# Power-Supply.net
KiCad netlist of a schematic drawn in Altium Designer
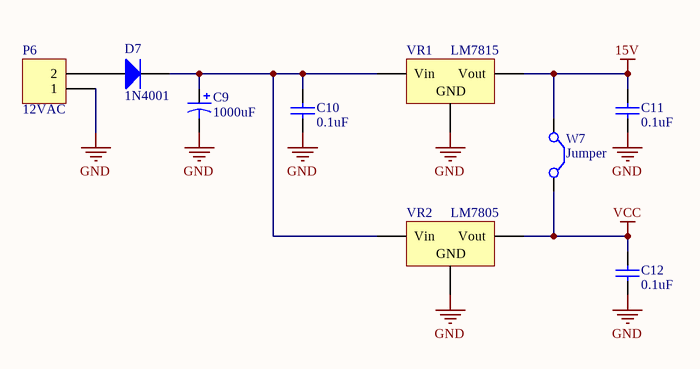
[diagram p0: Power-Supply.SchDoc]

(export (version "E")
  (design (tool "Eeschema 10.0.6"))
  (components
    (comp (ref "C9")
      (value "1000uF")
      (footprint "toko-Embedded:E3,5-10")
      (description "Polarized Capacitor (Radial)")
      (fields (field (name "PUBLISHER") "Altium Limited"))
      (libsource (lib "Miscellaneous Devices") (part "Cap Pol1"))
    )
    (comp (ref "C10")
      (value "0.1uF")
      (footprint "toko-Embedded:C025-024X044")
      (description "Capacitor")
      (fields (field (name "PUBLISHER") "Altium Limited"))
      (libsource (lib "Miscellaneous Devices") (part "Cap"))
    )
    (comp (ref "C11")
      (value "0.1uF")
      (footprint "toko-Embedded:C025-024X044")
      (description "Capacitor")
      (fields (field (name "PUBLISHER") "Altium Limited"))
      (libsource (lib "Miscellaneous Devices") (part "Cap"))
    )
    (comp (ref "C12")
      (value "0.1uF")
      (footprint "toko-Embedded:C025-024X044")
      (description "Capacitor")
      (fields (field (name "PUBLISHER") "Altium Limited"))
      (libsource (lib "Miscellaneous Devices") (part "Cap"))
    )
    (comp (ref "D7")
      (value "1N4001")
      (footprint "toko-Embedded:DO41-10")
      (description "Default Diode")
      (fields (field (name "PUBLISHER") "Altium Limited"))
      (libsource (lib "Miscellaneous Devices") (part "Diode"))
    )
    (comp (ref "P6")
      (value "12VAC")
      (footprint "toko-Embedded:6410-02")
      (description "Header, 2-Pin")
      (fields (field (name "PUBLISHER") "Altium Limited"))
      (libsource (lib "Miscellaneous Connectors") (part "Header 2"))
    )
    (comp (ref "VR1")
      (value "LM7815")
      (footprint "toko-Embedded:TO220V")
      (description "Voltage Regulator")
      (fields (field (name "PUBLISHER") "Altium Limited"))
      (libsource (lib "Miscellaneous Devices") (part "Volt Reg"))
    )
    (comp (ref "VR2")
      (value "LM7805")
      (footprint "toko-Embedded:TO220V")
      (description "Voltage Regulator")
      (fields (field (name "PUBLISHER") "Altium Limited"))
      (libsource (lib "Miscellaneous Devices") (part "Volt Reg"))
    )
    (comp (ref "W7")
      (value "Jumper")
      (footprint "Miscellaneous Connectors:HDR1X2")
      (description "Jumper Wire")
      (fields (field (name "PUBLISHER") "Altium Limited"))
      (libsource (lib "Miscellaneous Devices") (part "Jumper"))
    )
  )
  (nets
    (net (code "1") (name "15V") (class "Default")
      (node (ref "C11") (pin "2") (pinfunction "2_2") (pintype "passive"))
      (node (ref "VR1") (pin "3") (pinfunction "Vout_3") (pintype "passive"))
      (node (ref "W7") (pin "1") (pinfunction "C1_1") (pintype "passive"))
    )
    (net (code "2") (name "GND") (class "Default")
      (node (ref "C10") (pin "1") (pinfunction "1_1") (pintype "passive"))
      (node (ref "C11") (pin "1") (pinfunction "1_1") (pintype "passive"))
      (node (ref "C12") (pin "1") (pinfunction "1_1") (pintype "passive"))
      (node (ref "C9") (pin "2") (pinfunction "2_2") (pintype "passive"))
      (node (ref "P6") (pin "1") (pinfunction "1_1") (pintype "passive"))
      (node (ref "VR1") (pin "2") (pinfunction "GND_2") (pintype "passive"))
      (node (ref "VR2") (pin "2") (pinfunction "GND_2") (pintype "passive"))
    )
    (net (code "3") (name "Net-(D7-A)") (class "Default")
      (node (ref "D7") (pin "1") (pinfunction "A_1") (pintype "passive"))
      (node (ref "P6") (pin "2") (pinfunction "2_2") (pintype "passive"))
    )
    (net (code "4") (name "Net-(D7-K)") (class "Default")
      (node (ref "C10") (pin "2") (pinfunction "2_2") (pintype "passive"))
      (node (ref "C9") (pin "1") (pinfunction "1_1") (pintype "passive"))
      (node (ref "D7") (pin "2") (pinfunction "K_2") (pintype "passive"))
      (node (ref "VR1") (pin "1") (pinfunction "Vin_1") (pintype "passive"))
      (node (ref "VR2") (pin "1") (pinfunction "Vin_1") (pintype "passive"))
    )
    (net (code "5") (name "VCC") (class "Default")
      (node (ref "C12") (pin "2") (pinfunction "2_2") (pintype "passive"))
      (node (ref "VR2") (pin "3") (pinfunction "Vout_3") (pintype "passive"))
      (node (ref "W7") (pin "2") (pinfunction "C2_2") (pintype "passive"))
    )
  )
)
